# nuc5v2.net
KiCad netlist of a schematic drawn in Altium Designer
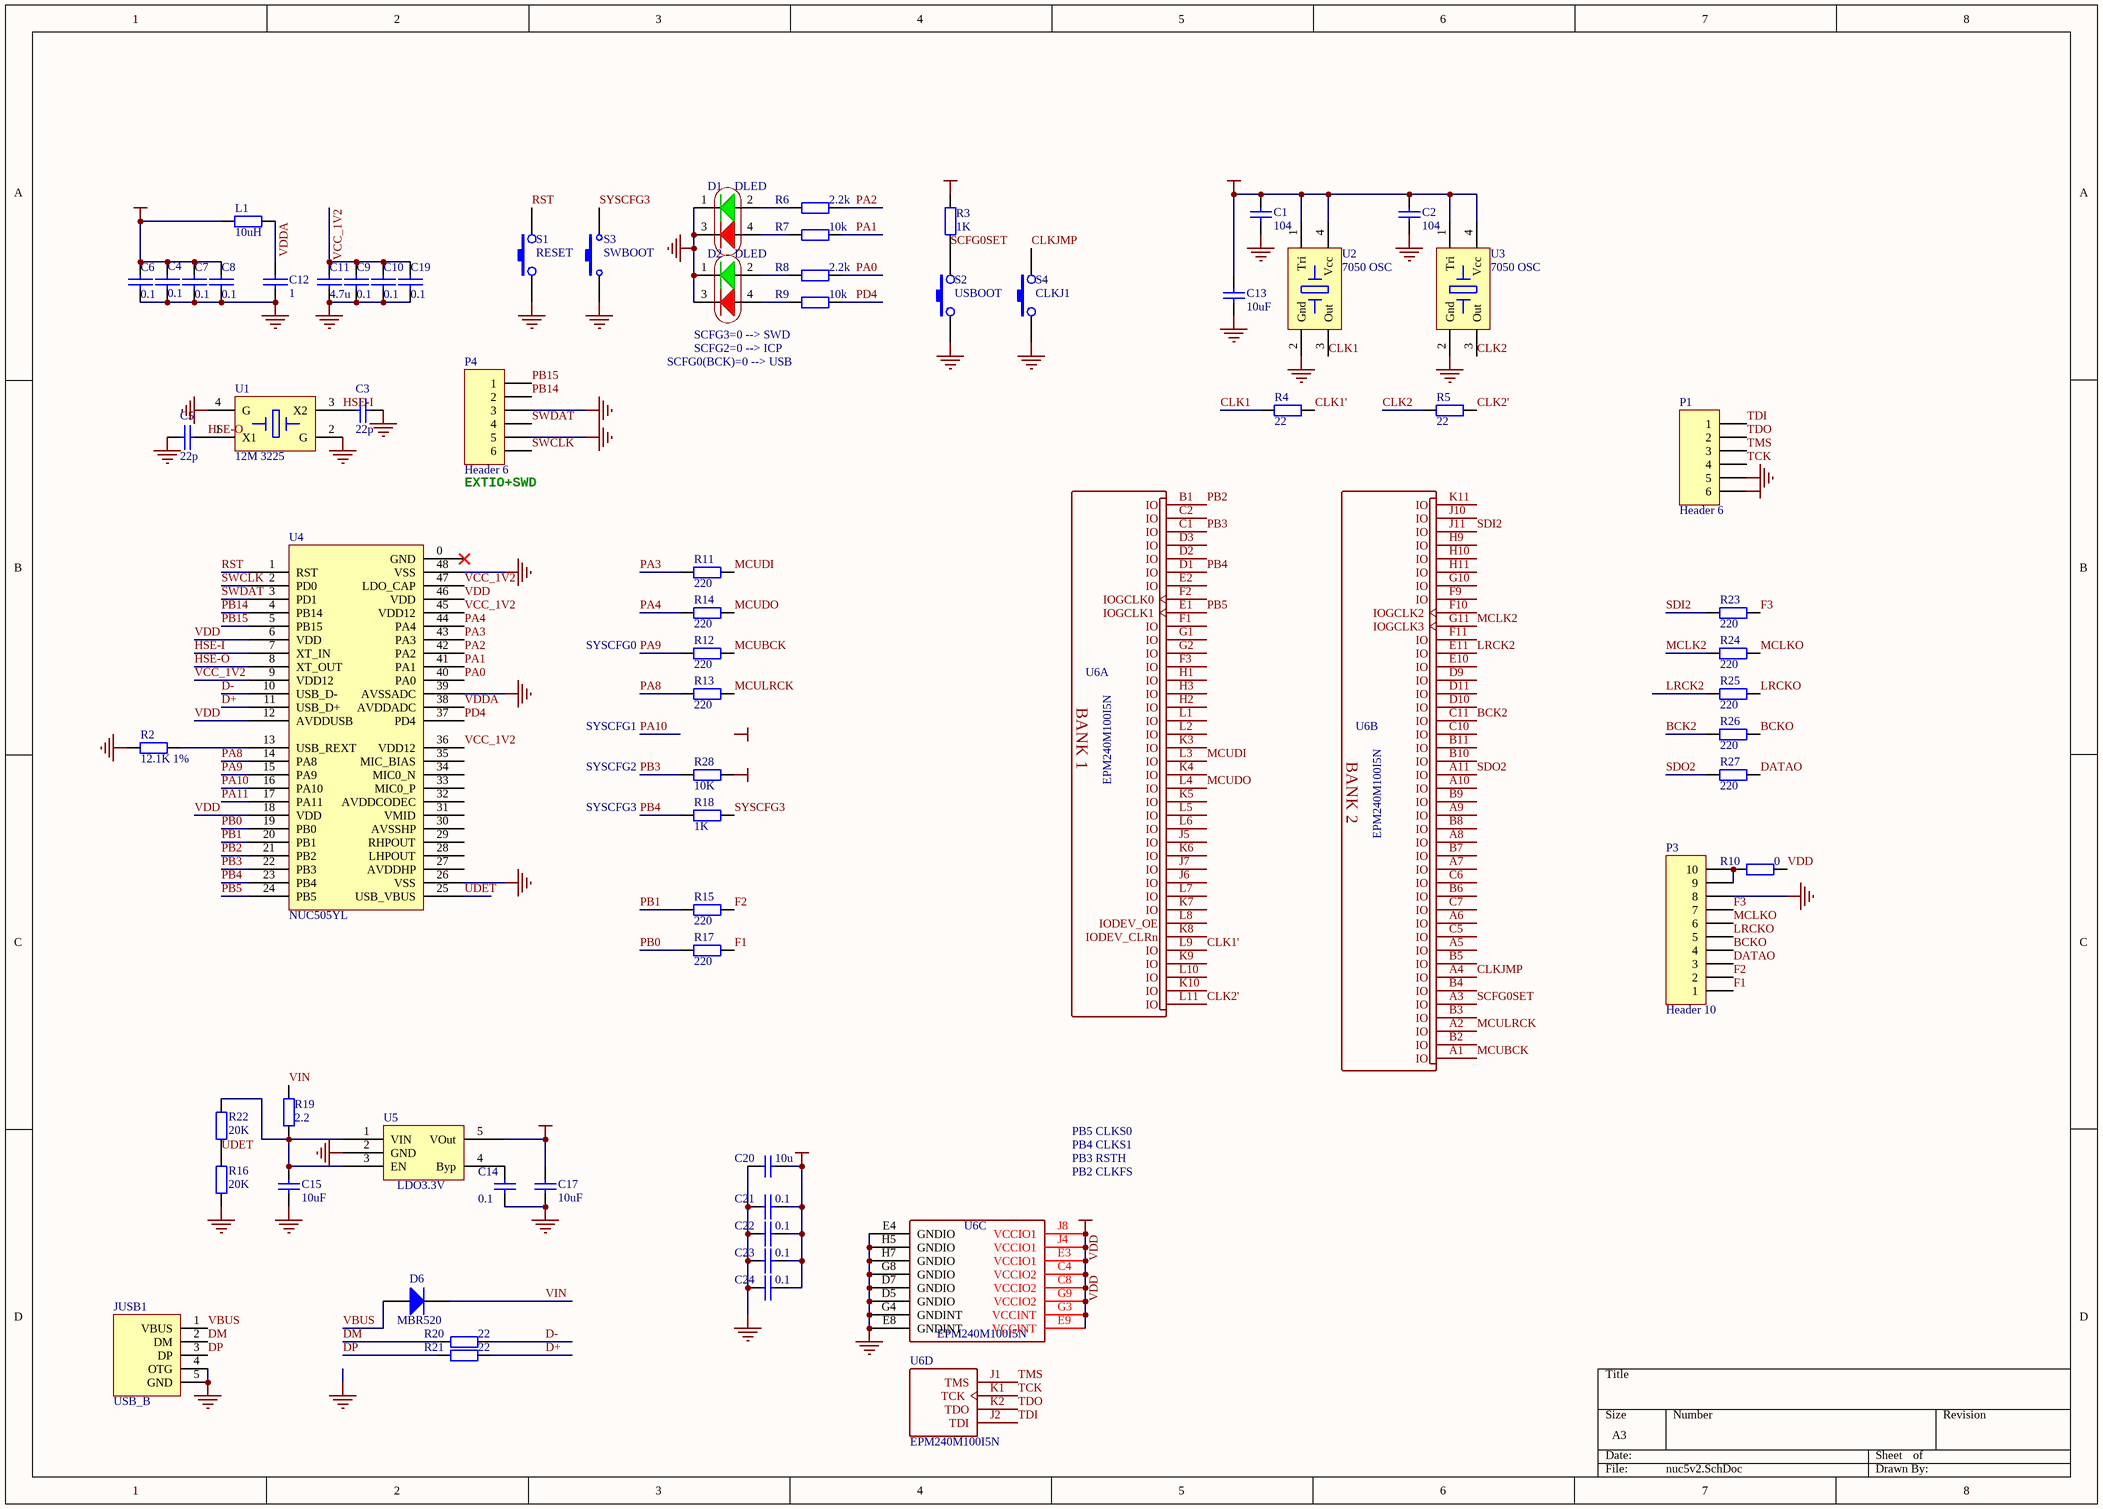
[diagram p0: nuc5v2.SchDoc]

(export (version "E")
  (design (tool "Eeschema 10.0.6"))
  (components
    (comp (ref "C1")
      (value "104")
      (footprint "CC0603CAP")
      (description "Capacitor0603")
      (libsource (lib "ADI1955-Sch") (part "Cap6"))
    )
    (comp (ref "C2")
      (value "104")
      (footprint "CC0603CAP")
      (description "Capacitor0603")
      (libsource (lib "ADI1955-Sch") (part "Cap6"))
    )
    (comp (ref "C3")
      (value "22p")
      (footprint "0603")
      (description "Capacitor")
      (libsource (lib "*") (part "CAP"))
    )
    (comp (ref "C4")
      (value "0.1")
      (footprint "0603")
      (description "Capacitor")
      (libsource (lib "*") (part "CAP"))
    )
    (comp (ref "C5")
      (value "22p")
      (footprint "0603")
      (description "Capacitor")
      (libsource (lib "") (part "CAP_1"))
    )
    (comp (ref "C6")
      (value "0.1")
      (footprint "0603")
      (description "Capacitor")
      (libsource (lib "*") (part "CAP"))
    )
    (comp (ref "C7")
      (value "0.1")
      (footprint "0603")
      (description "Capacitor")
      (libsource (lib "*") (part "CAP"))
    )
    (comp (ref "C8")
      (value "0.1")
      (footprint "0603")
      (description "Capacitor")
      (libsource (lib "*") (part "CAP"))
    )
    (comp (ref "C9")
      (value "0.1")
      (footprint "0603")
      (description "Capacitor")
      (libsource (lib "*") (part "CAP"))
    )
    (comp (ref "C10")
      (value "0.1")
      (footprint "0603")
      (description "Capacitor")
      (libsource (lib "*") (part "CAP"))
    )
    (comp (ref "C11")
      (value "4.7u")
      (footprint "0603")
      (description "Capacitor")
      (libsource (lib "*") (part "CAP"))
    )
    (comp (ref "C12")
      (value "1")
      (footprint "0603")
      (description "Capacitor")
      (libsource (lib "*") (part "CAP"))
    )
    (comp (ref "C13")
      (value "10uF")
      (footprint "CC0805CAP")
      (description "Capacitor0805")
      (libsource (lib "AudioLCR") (part "Cap8"))
    )
    (comp (ref "C14")
      (value "0.1")
      (footprint "0603")
      (description "Capacitor0805")
      (libsource (lib "*") (part "Cap8"))
    )
    (comp (ref "C15")
      (value "10uF")
      (footprint "CC0805CAP")
      (description "Capacitor0805")
      (libsource (lib "AudioLCR") (part "Cap8"))
    )
    (comp (ref "C17")
      (value "10uF")
      (footprint "CC0805CAP")
      (description "Capacitor0805")
      (libsource (lib "AudioLCR") (part "Cap8"))
    )
    (comp (ref "C19")
      (value "0.1")
      (footprint "0603")
      (description "Capacitor")
      (libsource (lib "*") (part "CAP"))
    )
    (comp (ref "C20")
      (value "10u")
      (footprint "CC0805CAP")
      (description "Capacitor0805")
      (libsource (lib "S1-LCR") (part "Cap8"))
    )
    (comp (ref "C21")
      (value "0.1")
      (footprint "0603")
      (description "Capacitor")
      (libsource (lib "*") (part "CAP"))
    )
    (comp (ref "C22")
      (value "0.1")
      (footprint "0603")
      (description "Capacitor")
      (libsource (lib "*") (part "CAP"))
    )
    (comp (ref "C23")
      (value "0.1")
      (footprint "0603")
      (description "Capacitor")
      (libsource (lib "*") (part "CAP"))
    )
    (comp (ref "C24")
      (value "0.1")
      (footprint "0603")
      (description "Capacitor")
      (libsource (lib "*") (part "CAP"))
    )
    (comp (ref "D1")
      (value "DLED")
      (footprint "LED1204")
      (description "1204双色LED")
      (libsource (lib "S1-常用") (part "LED1204"))
    )
    (comp (ref "D2")
      (value "DLED")
      (footprint "LED1204")
      (description "1204双色LED")
      (libsource (lib "S1-常用") (part "LED1204"))
    )
    (comp (ref "D6")
      (value "MBR520")
      (footprint "SOD123")
      (description "Default Diode")
      (libsource (lib "Miscellaneous Devices") (part "Diode"))
    )
    (comp (ref "JUSB1")
      (value "USB_B")
      (footprint "USB-B-M")
      (description "USB Mini/Micro 5P")
      (libsource (lib "AudioLCR") (part "USB_B"))
    )
    (comp (ref "L1")
      (value "10uH")
      (footprint "CC0805RES")
      (description "Resistor0805")
      (libsource (lib "ADI1955-Sch") (part "Res8"))
    )
    (comp (ref "P1")
      (value "Header 6")
      (footprint "密脚针1.27mm*6")
      (description "Header, 6-Pin")
      (fields (field (name "PUBLISHER") "Altium Limited"))
      (libsource (lib "Miscellaneous Connectors") (part "Header 6"))
    )
    (comp (ref "P3")
      (value "Header 10")
      (footprint "HDR1X10")
      (description "Header, 10-Pin")
      (fields (field (name "PUBLISHER") "Altium Limited"))
      (libsource (lib "Miscellaneous Connectors") (part "Header 10"))
    )
    (comp (ref "P4")
      (value "Header 6")
      (footprint "密脚针1.27mm*6")
      (description "Header, 6-Pin")
      (fields (field (name "PUBLISHER") "Altium Limited"))
      (libsource (lib "Miscellaneous Connectors") (part "Header 6"))
    )
    (comp (ref "R2")
      (value "12.1K 1%")
      (footprint "CR1005-0402")
      (description "Resistor0603")
      (libsource (lib "S1-LCR") (part "Res6"))
    )
    (comp (ref "R3")
      (value "1K")
      (footprint "CR1005-0402")
      (description "Resistor0603")
      (libsource (lib "") (part "Res6_1"))
    )
    (comp (ref "R4")
      (value "22")
      (footprint "CR1005-0402")
      (description "Resistor0603")
      (libsource (lib "*") (part "Res6"))
    )
    (comp (ref "R5")
      (value "22")
      (footprint "CR1005-0402")
      (description "Resistor0603")
      (libsource (lib "*") (part "Res6"))
    )
    (comp (ref "R6")
      (value "2.2k")
      (footprint "CR1005-0402")
      (description "Resistor0603")
      (libsource (lib "ADI1955-Sch") (part "Res6"))
    )
    (comp (ref "R7")
      (value "10k")
      (footprint "CR1005-0402")
      (description "Resistor0603")
      (libsource (lib "ADI1955-Sch") (part "Res6"))
    )
    (comp (ref "R8")
      (value "2.2k")
      (footprint "CR1005-0402")
      (description "Resistor0603")
      (libsource (lib "ADI1955-Sch") (part "Res6"))
    )
    (comp (ref "R9")
      (value "10k")
      (footprint "CR1005-0402")
      (description "Resistor0603")
      (libsource (lib "ADI1955-Sch") (part "Res6"))
    )
    (comp (ref "R10")
      (value "0")
      (footprint "0603")
      (description "Resistor0603")
      (libsource (lib "ADI1955-Sch") (part "Res6"))
    )
    (comp (ref "R11")
      (value "220")
      (footprint "CR1005-0402")
      (description "Resistor0603")
      (libsource (lib "*") (part "Res6"))
    )
    (comp (ref "R12")
      (value "220")
      (footprint "CR1005-0402")
      (description "Resistor0603")
      (libsource (lib "") (part "Res6_2"))
    )
    (comp (ref "R13")
      (value "220")
      (footprint "CR1005-0402")
      (description "Resistor0603")
      (libsource (lib "*") (part "Res6"))
    )
    (comp (ref "R14")
      (value "220")
      (footprint "CR1005-0402")
      (description "Resistor0603")
      (libsource (lib "ADI1955-Sch") (part "Res6"))
    )
    (comp (ref "R15")
      (value "220")
      (footprint "CR1005-0402")
      (description "Resistor0603")
      (libsource (lib "ADI1955-Sch") (part "Res6"))
    )
    (comp (ref "R16")
      (value "20K")
      (footprint "CR1005-0402")
      (description "贴片电阻")
      (libsource (lib "MY LIB") (part "R"))
    )
    (comp (ref "R17")
      (value "220")
      (footprint "CR1005-0402")
      (description "Resistor0603")
      (libsource (lib "ADI1955-Sch") (part "Res6"))
    )
    (comp (ref "R18")
      (value "1K")
      (footprint "CR1005-0402")
      (description "Resistor0603")
      (libsource (lib "*") (part "Res6"))
    )
    (comp (ref "R19")
      (value "2.2")
      (footprint "CC0603RES")
      (description "Resistor0603")
      (libsource (lib "AudioLCR") (part "Res6"))
    )
    (comp (ref "R20")
      (value "22")
      (footprint "CR1005-0402")
      (description "Resistor0603")
      (libsource (lib "ADI1955-Sch") (part "Res6"))
    )
    (comp (ref "R21")
      (value "22")
      (footprint "CR1005-0402")
      (description "Resistor0603")
      (libsource (lib "ADI1955-Sch") (part "Res6"))
    )
    (comp (ref "R22")
      (value "20K")
      (footprint "CR1005-0402")
      (description "贴片电阻")
      (libsource (lib "MY LIB") (part "R"))
    )
    (comp (ref "R23")
      (value "220")
      (footprint "CR1005-0402")
      (description "Resistor0603")
      (libsource (lib "*") (part "Res6"))
    )
    (comp (ref "R24")
      (value "220")
      (footprint "CR1005-0402")
      (description "Resistor0603")
      (libsource (lib "ADI1955-Sch") (part "Res6"))
    )
    (comp (ref "R25")
      (value "220")
      (footprint "CR1005-0402")
      (description "Resistor0603")
      (libsource (lib "") (part "Res6_2"))
    )
    (comp (ref "R26")
      (value "220")
      (footprint "CR1005-0402")
      (description "Resistor0603")
      (libsource (lib "*") (part "Res6"))
    )
    (comp (ref "R27")
      (value "220")
      (footprint "CR1005-0402")
      (description "Resistor0603")
      (libsource (lib "*") (part "Res6"))
    )
    (comp (ref "R28")
      (value "10K")
      (footprint "CR1005-0402")
      (description "Resistor0603")
      (libsource (lib "*") (part "Res6"))
    )
    (comp (ref "S1") (value "RESET") (footprint "密脚针1.27mm*2") (libsource (lib "*") (part "SW-PB")))
    (comp (ref "S2") (value "USBOOT") (footprint "密脚针1.27mm*2") (libsource (lib "*") (part "SW-PB")))
    (comp (ref "S3")
      (value "SWBOOT")
      (footprint "密脚针1.27mm*2")
      (description "Switch")
      (fields (field (name "PUBLISHER") "Altium Limited"))
      (libsource (lib "Miscellaneous Devices") (part "SW-PB"))
    )
    (comp (ref "S4") (value "CLKJ1") (footprint "密脚针1.27mm*2") (libsource (lib "*") (part "SW-PB")))
    (comp (ref "U1") (value "12M 3225") (footprint "OSC-3225") (libsource (lib "AudioLCR") (part "XTAL")))
    (comp (ref "U2") (value "7050 OSC") (footprint "OSC-3225") (libsource (lib "AudioLCR") (part "XTAL_OSC")))
    (comp (ref "U3") (value "7050 OSC") (footprint "OSC-3225") (libsource (lib "AudioLCR") (part "XTAL_OSC")))
    (comp (ref "U4") (value "NUC505YL") (footprint "LQFP-48") (libsource (lib "NUC505YL") (part "NUC505YL")))
    (comp (ref "U5")
      (value "LDO3.3V")
      (footprint "SOT23-5")
      (description "LP2985 5V LDO")
      (libsource (lib "ADI1955-Sch") (part "LP2985-5"))
    )
    (comp (ref "U6")
      (value "EPM240M100I5N")
      (footprint "MBGA100")
      (fields (field (name "SUBPART_NO") "1"))
      (libsource (lib "S2-芯片") (part "EPM240M100I5N"))
    )
  )
  (nets
    (net (code "1") (name "/BCK2") (class "Default")
      (node (ref "R26") (pin "1") (pinfunction "1_1") (pintype "passive"))
      (node (ref "U6") (pin "C11") (pinfunction "IO_C11") (pintype "passive"))
    )
    (net (code "2") (name "/BCKO") (class "Default")
      (node (ref "P3") (pin "4") (pinfunction "4_4") (pintype "passive"))
      (node (ref "R26") (pin "2") (pinfunction "2_2") (pintype "passive"))
    )
    (net (code "3") (name "/CLK1") (class "Default")
      (node (ref "R4") (pin "1") (pinfunction "1_1") (pintype "passive"))
      (node (ref "U2") (pin "3") (pinfunction "Out_3") (pintype "passive"))
    )
    (net (code "4") (name "/CLK1'") (class "Default")
      (node (ref "R4") (pin "2") (pinfunction "2_2") (pintype "passive"))
      (node (ref "U6") (pin "L9") (pinfunction "IO_L9") (pintype "passive"))
    )
    (net (code "5") (name "/CLK2") (class "Default")
      (node (ref "R5") (pin "1") (pinfunction "1_1") (pintype "passive"))
      (node (ref "U3") (pin "3") (pinfunction "Out_3") (pintype "passive"))
    )
    (net (code "6") (name "/CLK2'") (class "Default")
      (node (ref "R5") (pin "2") (pinfunction "2_2") (pintype "passive"))
      (node (ref "U6") (pin "L11") (pinfunction "IO_L11") (pintype "passive"))
    )
    (net (code "7") (name "/CLKJMP") (class "Default")
      (node (ref "S4") (pin "2") (pinfunction "2_2") (pintype "passive"))
      (node (ref "U6") (pin "A4") (pinfunction "IO_A4") (pintype "passive"))
    )
    (net (code "8") (name "/D+") (class "Default")
      (node (ref "R21") (pin "1") (pinfunction "1_1") (pintype "passive"))
      (node (ref "U4") (pin "11") (pinfunction "USB_D+_11") (pintype "passive"))
    )
    (net (code "9") (name "/D-") (class "Default")
      (node (ref "R20") (pin "1") (pinfunction "1_1") (pintype "passive"))
      (node (ref "U4") (pin "10") (pinfunction "USB_D-_10") (pintype "passive"))
    )
    (net (code "10") (name "/DATAO") (class "Default")
      (node (ref "P3") (pin "3") (pinfunction "3_3") (pintype "passive"))
      (node (ref "R27") (pin "2") (pinfunction "2_2") (pintype "passive"))
    )
    (net (code "11") (name "/DM") (class "Default")
      (node (ref "JUSB1") (pin "2") (pinfunction "DM_2") (pintype "passive"))
      (node (ref "R20") (pin "2") (pinfunction "2_2") (pintype "passive"))
    )
    (net (code "12") (name "/DP") (class "Default")
      (node (ref "JUSB1") (pin "3") (pinfunction "DP_3") (pintype "passive"))
      (node (ref "R21") (pin "2") (pinfunction "2_2") (pintype "passive"))
    )
    (net (code "13") (name "/F1") (class "Default")
      (node (ref "P3") (pin "1") (pinfunction "1_1") (pintype "passive"))
      (node (ref "R17") (pin "1") (pinfunction "1_1") (pintype "passive"))
    )
    (net (code "14") (name "/F2") (class "Default")
      (node (ref "P3") (pin "2") (pinfunction "2_2") (pintype "passive"))
      (node (ref "R15") (pin "1") (pinfunction "1_1") (pintype "passive"))
    )
    (net (code "15") (name "/F3") (class "Default")
      (node (ref "P3") (pin "7") (pinfunction "7_7") (pintype "passive"))
      (node (ref "R23") (pin "2") (pinfunction "2_2") (pintype "passive"))
    )
    (net (code "16") (name "/HSE-I") (class "Default")
      (node (ref "C3") (pin "1") (pinfunction "1_1") (pintype "passive"))
      (node (ref "U1") (pin "3") (pinfunction "X2_3") (pintype "passive"))
      (node (ref "U4") (pin "7") (pinfunction "XT_IN_7") (pintype "passive"))
    )
    (net (code "17") (name "/HSE-O") (class "Default")
      (node (ref "C5") (pin "2") (pinfunction "2_2") (pintype "passive"))
      (node (ref "U1") (pin "1") (pinfunction "X1_1") (pintype "passive"))
      (node (ref "U4") (pin "8") (pinfunction "XT_OUT_8") (pintype "passive"))
    )
    (net (code "18") (name "/LRCK2") (class "Default")
      (node (ref "R25") (pin "2") (pinfunction "2_2") (pintype "passive"))
      (node (ref "U6") (pin "E11") (pinfunction "IO_E11") (pintype "passive"))
    )
    (net (code "19") (name "/LRCKO") (class "Default")
      (node (ref "P3") (pin "5") (pinfunction "5_5") (pintype "passive"))
      (node (ref "R25") (pin "1") (pinfunction "1_1") (pintype "passive"))
    )
    (net (code "20") (name "/MCLK2") (class "Default")
      (node (ref "R24") (pin "2") (pinfunction "2_2") (pintype "passive"))
      (node (ref "U6") (pin "G11") (pinfunction "IOGCLK3_G11") (pintype "passive"))
    )
    (net (code "21") (name "/MCLKO") (class "Default")
      (node (ref "P3") (pin "6") (pinfunction "6_6") (pintype "passive"))
      (node (ref "R24") (pin "1") (pinfunction "1_1") (pintype "passive"))
    )
    (net (code "22") (name "/MCUBCK") (class "Default")
      (node (ref "R12") (pin "1") (pinfunction "1_1") (pintype "passive"))
      (node (ref "U6") (pin "A1") (pinfunction "IO_A1") (pintype "passive"))
    )
    (net (code "23") (name "/MCUDI") (class "Default")
      (node (ref "R11") (pin "2") (pinfunction "2_2") (pintype "passive"))
      (node (ref "U6") (pin "L3") (pinfunction "IO_L3") (pintype "passive"))
    )
    (net (code "24") (name "/MCUDO") (class "Default")
      (node (ref "R14") (pin "1") (pinfunction "1_1") (pintype "passive"))
      (node (ref "U6") (pin "L4") (pinfunction "IO_L4") (pintype "passive"))
    )
    (net (code "25") (name "/MCULRCK") (class "Default")
      (node (ref "R13") (pin "2") (pinfunction "2_2") (pintype "passive"))
      (node (ref "U6") (pin "A2") (pinfunction "IO_A2") (pintype "passive"))
    )
    (net (code "26") (name "/PA0") (class "Default")
      (node (ref "R8") (pin "1") (pinfunction "1_1") (pintype "passive"))
      (node (ref "U4") (pin "40") (pinfunction "PA0_40") (pintype "passive"))
    )
    (net (code "27") (name "/PA1") (class "Default")
      (node (ref "R7") (pin "1") (pinfunction "1_1") (pintype "passive"))
      (node (ref "U4") (pin "41") (pinfunction "PA1_41") (pintype "passive"))
    )
    (net (code "28") (name "/PA2") (class "Default")
      (node (ref "R6") (pin "1") (pinfunction "1_1") (pintype "passive"))
      (node (ref "U4") (pin "42") (pinfunction "PA2_42") (pintype "passive"))
    )
    (net (code "29") (name "/PA3") (class "Default")
      (node (ref "R11") (pin "1") (pinfunction "1_1") (pintype "passive"))
      (node (ref "U4") (pin "43") (pinfunction "PA3_43") (pintype "passive"))
    )
    (net (code "30") (name "/PA4") (class "Default")
      (node (ref "R14") (pin "2") (pinfunction "2_2") (pintype "passive"))
      (node (ref "U4") (pin "44") (pinfunction "PA4_44") (pintype "passive"))
    )
    (net (code "31") (name "/PA8") (class "Default")
      (node (ref "R13") (pin "1") (pinfunction "1_1") (pintype "passive"))
      (node (ref "U4") (pin "14") (pinfunction "PA8_14") (pintype "passive"))
    )
    (net (code "32") (name "/PA9") (class "Default")
      (node (ref "R12") (pin "2") (pinfunction "2_2") (pintype "passive"))
      (node (ref "U4") (pin "15") (pinfunction "PA9_15") (pintype "passive"))
    )
    (net (code "33") (name "/PA10") (class "Default")
      (node (ref "U4") (pin "16") (pinfunction "PA10_16") (pintype "passive"))
    )
    (net (code "34") (name "/PA11") (class "Default")
      (node (ref "U4") (pin "17") (pinfunction "PA11_17") (pintype "passive"))
    )
    (net (code "35") (name "/PB0") (class "Default")
      (node (ref "R17") (pin "2") (pinfunction "2_2") (pintype "passive"))
      (node (ref "U4") (pin "19") (pinfunction "PB0_19") (pintype "passive"))
    )
    (net (code "36") (name "/PB1") (class "Default")
      (node (ref "R15") (pin "2") (pinfunction "2_2") (pintype "passive"))
      (node (ref "U4") (pin "20") (pinfunction "PB1_20") (pintype "passive"))
    )
    (net (code "37") (name "/PB2") (class "Default")
      (node (ref "U4") (pin "21") (pinfunction "PB2_21") (pintype "passive"))
      (node (ref "U6") (pin "B1") (pinfunction "IO_B1") (pintype "passive"))
    )
    (net (code "38") (name "/PB3") (class "Default")
      (node (ref "R28") (pin "1") (pinfunction "1_1") (pintype "passive"))
      (node (ref "U4") (pin "22") (pinfunction "PB3_22") (pintype "passive"))
      (node (ref "U6") (pin "C1") (pinfunction "IO_C1") (pintype "passive"))
    )
    (net (code "39") (name "/PB4") (class "Default")
      (node (ref "R18") (pin "1") (pinfunction "1_1") (pintype "passive"))
      (node (ref "U4") (pin "23") (pinfunction "PB4_23") (pintype "passive"))
      (node (ref "U6") (pin "D1") (pinfunction "IO_D1") (pintype "passive"))
    )
    (net (code "40") (name "/PB5") (class "Default")
      (node (ref "U4") (pin "24") (pinfunction "PB5_24") (pintype "passive"))
      (node (ref "U6") (pin "E1") (pinfunction "IOGCLK1_E1") (pintype "passive"))
    )
    (net (code "41") (name "/PB14") (class "Default")
      (node (ref "P4") (pin "2") (pinfunction "2_2") (pintype "passive"))
      (node (ref "U4") (pin "4") (pinfunction "PB14_4") (pintype "passive"))
    )
    (net (code "42") (name "/PB15") (class "Default")
      (node (ref "P4") (pin "1") (pinfunction "1_1") (pintype "passive"))
      (node (ref "U4") (pin "5") (pinfunction "PB15_5") (pintype "passive"))
    )
    (net (code "43") (name "/PD4") (class "Default")
      (node (ref "R9") (pin "1") (pinfunction "1_1") (pintype "passive"))
      (node (ref "U4") (pin "37") (pinfunction "PD4_37") (pintype "passive"))
    )
    (net (code "44") (name "/RST") (class "Default")
      (node (ref "S1") (pin "2") (pinfunction "2_2") (pintype "passive"))
      (node (ref "U4") (pin "1") (pinfunction "RST_1") (pintype "passive"))
    )
    (net (code "45") (name "/SCFG0SET") (class "Default")
      (node (ref "R3") (pin "1") (pinfunction "1_1") (pintype "passive"))
      (node (ref "S2") (pin "2") (pinfunction "2_2") (pintype "passive"))
      (node (ref "U6") (pin "A3") (pinfunction "IO_A3") (pintype "passive"))
    )
    (net (code "46") (name "/SDI2") (class "Default")
      (node (ref "R23") (pin "1") (pinfunction "1_1") (pintype "passive"))
      (node (ref "U6") (pin "J11") (pinfunction "IO_J11") (pintype "passive"))
    )
    (net (code "47") (name "/SDO2") (class "Default")
      (node (ref "R27") (pin "1") (pinfunction "1_1") (pintype "passive"))
      (node (ref "U6") (pin "A11") (pinfunction "IO_A11") (pintype "passive"))
    )
    (net (code "48") (name "/SWCLK") (class "Default")
      (node (ref "P4") (pin "6") (pinfunction "6_6") (pintype "passive"))
      (node (ref "U4") (pin "2") (pinfunction "PD0_2") (pintype "passive"))
    )
    (net (code "49") (name "/SWDAT") (class "Default")
      (node (ref "P4") (pin "4") (pinfunction "4_4") (pintype "passive"))
      (node (ref "U4") (pin "3") (pinfunction "PD1_3") (pintype "passive"))
    )
    (net (code "50") (name "/SYSCFG3") (class "Default")
      (node (ref "R18") (pin "2") (pinfunction "2_2") (pintype "passive"))
      (node (ref "S3") (pin "2") (pinfunction "2_2") (pintype "passive"))
    )
    (net (code "51") (name "/TCK") (class "Default")
      (node (ref "P1") (pin "4") (pinfunction "4_4") (pintype "passive"))
      (node (ref "U6") (pin "K1") (pinfunction "TCK_K1") (pintype "passive"))
    )
    (net (code "52") (name "/TDI") (class "Default")
      (node (ref "P1") (pin "1") (pinfunction "1_1") (pintype "passive"))
      (node (ref "U6") (pin "J2") (pinfunction "TDI_J2") (pintype "passive"))
    )
    (net (code "53") (name "/TDO") (class "Default")
      (node (ref "P1") (pin "2") (pinfunction "2_2") (pintype "passive"))
      (node (ref "U6") (pin "K2") (pinfunction "TDO_K2") (pintype "passive"))
    )
    (net (code "54") (name "/TMS") (class "Default")
      (node (ref "P1") (pin "3") (pinfunction "3_3") (pintype "passive"))
      (node (ref "U6") (pin "J1") (pinfunction "TMS_J1") (pintype "passive"))
    )
    (net (code "55") (name "/UDET") (class "Default")
      (node (ref "R16") (pin "2") (pinfunction "2_2") (pintype "passive"))
      (node (ref "R22") (pin "1") (pinfunction "1_1") (pintype "passive"))
      (node (ref "U4") (pin "25") (pinfunction "USB_VBUS_25") (pintype "passive"))
    )
    (net (code "56") (name "/VBUS") (class "Default")
      (node (ref "D6") (pin "1") (pinfunction "A_1") (pintype "passive"))
      (node (ref "JUSB1") (pin "1") (pinfunction "VBUS_1") (pintype "passive"))
    )
    (net (code "57") (name "/VCC_1V2") (class "Default")
      (node (ref "C10") (pin "1") (pinfunction "1_1") (pintype "passive"))
      (node (ref "C11") (pin "1") (pinfunction "1_1") (pintype "passive"))
      (node (ref "C19") (pin "1") (pinfunction "1_1") (pintype "passive"))
      (node (ref "C9") (pin "1") (pinfunction "1_1") (pintype "passive"))
      (node (ref "U4") (pin "36") (pinfunction "VDD12_36") (pintype "passive"))
      (node (ref "U4") (pin "45") (pinfunction "VDD12_45") (pintype "passive"))
      (node (ref "U4") (pin "47") (pinfunction "LDO_CAP_47") (pintype "passive"))
      (node (ref "U4") (pin "9") (pinfunction "VDD12_9") (pintype "passive"))
    )
    (net (code "58") (name "/VDDA") (class "Default")
      (node (ref "C12") (pin "1") (pinfunction "1_1") (pintype "passive"))
      (node (ref "L1") (pin "2") (pinfunction "2_2") (pintype "passive"))
      (node (ref "U4") (pin "38") (pinfunction "AVDDADC_38") (pintype "passive"))
    )
    (net (code "59") (name "/VIN") (class "Default")
      (node (ref "D6") (pin "2") (pinfunction "K_2") (pintype "passive"))
      (node (ref "R19") (pin "1") (pinfunction "1_1") (pintype "passive"))
    )
    (net (code "60") (name "GND") (class "Default")
      (node (ref "C1") (pin "1") (pinfunction "1_1") (pintype "passive"))
      (node (ref "C10") (pin "2") (pinfunction "2_2") (pintype "passive"))
      (node (ref "C11") (pin "2") (pinfunction "2_2") (pintype "passive"))
      (node (ref "C12") (pin "2") (pinfunction "2_2") (pintype "passive"))
      (node (ref "C13") (pin "1") (pinfunction "1_1") (pintype "passive"))
      (node (ref "C14") (pin "2") (pinfunction "2_2") (pintype "passive"))
      (node (ref "C15") (pin "1") (pinfunction "1_1") (pintype "passive"))
      (node (ref "C17") (pin "1") (pinfunction "1_1") (pintype "passive"))
      (node (ref "C19") (pin "2") (pinfunction "2_2") (pintype "passive"))
      (node (ref "C2") (pin "2") (pinfunction "2_2") (pintype "passive"))
      (node (ref "C20") (pin "2") (pinfunction "2_2") (pintype "passive"))
      (node (ref "C21") (pin "1") (pinfunction "1_1") (pintype "passive"))
      (node (ref "C22") (pin "1") (pinfunction "1_1") (pintype "passive"))
      (node (ref "C23") (pin "1") (pinfunction "1_1") (pintype "passive"))
      (node (ref "C24") (pin "1") (pinfunction "1_1") (pintype "passive"))
      (node (ref "C3") (pin "2") (pinfunction "2_2") (pintype "passive"))
      (node (ref "C4") (pin "2") (pinfunction "2_2") (pintype "passive"))
      (node (ref "C5") (pin "1") (pinfunction "1_1") (pintype "passive"))
      (node (ref "C6") (pin "2") (pinfunction "2_2") (pintype "passive"))
      (node (ref "C7") (pin "1") (pinfunction "1_1") (pintype "passive"))
      (node (ref "C8") (pin "2") (pinfunction "2_2") (pintype "passive"))
      (node (ref "C9") (pin "2") (pinfunction "2_2") (pintype "passive"))
      (node (ref "D1") (pin "1") (pinfunction "1_1") (pintype "passive"))
      (node (ref "D1") (pin "3") (pinfunction "3_3") (pintype "passive"))
      (node (ref "D2") (pin "1") (pinfunction "1_1") (pintype "passive"))
      (node (ref "D2") (pin "3") (pinfunction "3_3") (pintype "passive"))
      (node (ref "JUSB1") (pin "4") (pinfunction "OTG_4") (pintype "passive"))
      (node (ref "JUSB1") (pin "5") (pinfunction "GND_5") (pintype "passive"))
      (node (ref "P1") (pin "5") (pinfunction "5_5") (pintype "passive"))
      (node (ref "P3") (pin "8") (pinfunction "8_8") (pintype "passive"))
      (node (ref "P4") (pin "3") (pinfunction "3_3") (pintype "passive"))
      (node (ref "P4") (pin "5") (pinfunction "5_5") (pintype "passive"))
      (node (ref "R16") (pin "1") (pinfunction "1_1") (pintype "passive"))
      (node (ref "R2") (pin "2") (pinfunction "2_2") (pintype "passive"))
      (node (ref "S1") (pin "1") (pinfunction "1_1") (pintype "passive"))
      (node (ref "S2") (pin "1") (pinfunction "1_1") (pintype "passive"))
      (node (ref "S3") (pin "1") (pinfunction "1_1") (pintype "passive"))
      (node (ref "S4") (pin "1") (pinfunction "1_1") (pintype "passive"))
      (node (ref "U1") (pin "2") (pinfunction "G_2") (pintype "passive"))
      (node (ref "U1") (pin "4") (pinfunction "G_4") (pintype "passive"))
      (node (ref "U2") (pin "2") (pinfunction "Gnd_2") (pintype "passive"))
      (node (ref "U3") (pin "2") (pinfunction "Gnd_2") (pintype "passive"))
      (node (ref "U4") (pin "26") (pinfunction "VSS_26") (pintype "passive"))
      (node (ref "U4") (pin "39") (pinfunction "AVSSADC_39") (pintype "passive"))
      (node (ref "U4") (pin "48") (pinfunction "VSS_48") (pintype "passive"))
      (node (ref "U5") (pin "2") (pinfunction "GND_2") (pintype "passive"))
      (node (ref "U6") (pin "D5") (pinfunction "GNDIO_D5") (pintype "passive"))
      (node (ref "U6") (pin "D7") (pinfunction "GNDIO_D7") (pintype "passive"))
      (node (ref "U6") (pin "E4") (pinfunction "GNDIO_E4") (pintype "passive"))
      (node (ref "U6") (pin "E8") (pinfunction "GNDINT_E8") (pintype "passive"))
      (node (ref "U6") (pin "G4") (pinfunction "GNDINT_G4") (pintype "passive"))
      (node (ref "U6") (pin "G8") (pinfunction "GNDIO_G8") (pintype "passive"))
      (node (ref "U6") (pin "H5") (pinfunction "GNDIO_H5") (pintype "passive"))
      (node (ref "U6") (pin "H7") (pinfunction "GNDIO_H7") (pintype "passive"))
    )
    (net (code "61") (name "Net-(D1-Pad2)") (class "Default")
      (node (ref "D1") (pin "2") (pinfunction "2_2") (pintype "passive"))
      (node (ref "R6") (pin "2") (pinfunction "2_2") (pintype "passive"))
    )
    (net (code "62") (name "Net-(D1-Pad4)") (class "Default")
      (node (ref "D1") (pin "4") (pinfunction "4_4") (pintype "passive"))
      (node (ref "R7") (pin "2") (pinfunction "2_2") (pintype "passive"))
    )
    (net (code "63") (name "Net-(D2-Pad2)") (class "Default")
      (node (ref "D2") (pin "2") (pinfunction "2_2") (pintype "passive"))
      (node (ref "R8") (pin "2") (pinfunction "2_2") (pintype "passive"))
    )
    (net (code "64") (name "Net-(D2-Pad4)") (class "Default")
      (node (ref "D2") (pin "4") (pinfunction "4_4") (pintype "passive"))
      (node (ref "R9") (pin "2") (pinfunction "2_2") (pintype "passive"))
    )
    (net (code "65") (name "Net-(P3-Pad10)") (class "Default")
      (node (ref "P3") (pin "10") (pinfunction "10_10") (pintype "passive"))
      (node (ref "P3") (pin "9") (pinfunction "9_9") (pintype "passive"))
      (node (ref "R10") (pin "2") (pinfunction "2_2") (pintype "passive"))
    )
    (net (code "66") (name "Net-(U4-USB_REXT)") (class "Default")
      (node (ref "R2") (pin "1") (pinfunction "1_1") (pintype "passive"))
      (node (ref "U4") (pin "13") (pinfunction "USB_REXT_13") (pintype "passive"))
    )
    (net (code "67") (name "Net-(U5-Byp)") (class "Default")
      (node (ref "C14") (pin "1") (pinfunction "1_1") (pintype "passive"))
      (node (ref "U5") (pin "4") (pinfunction "Byp_4") (pintype "passive"))
    )
    (net (code "68") (name "Net-(U5-EN)") (class "Default")
      (node (ref "C15") (pin "2") (pinfunction "2_2") (pintype "passive"))
      (node (ref "R19") (pin "2") (pinfunction "2_2") (pintype "passive"))
      (node (ref "R22") (pin "2") (pinfunction "2_2") (pintype "passive"))
      (node (ref "U5") (pin "1") (pinfunction "VIN_1") (pintype "passive"))
      (node (ref "U5") (pin "3") (pinfunction "EN_3") (pintype "passive"))
    )
    (net (code "69") (name "VDD") (class "Default")
      (node (ref "C1") (pin "2") (pinfunction "2_2") (pintype "passive"))
      (node (ref "C13") (pin "2") (pinfunction "2_2") (pintype "passive"))
      (node (ref "C17") (pin "2") (pinfunction "2_2") (pintype "passive"))
      (node (ref "C2") (pin "1") (pinfunction "1_1") (pintype "passive"))
      (node (ref "C20") (pin "1") (pinfunction "1_1") (pintype "passive"))
      (node (ref "C21") (pin "2") (pinfunction "2_2") (pintype "passive"))
      (node (ref "C22") (pin "2") (pinfunction "2_2") (pintype "passive"))
      (node (ref "C23") (pin "2") (pinfunction "2_2") (pintype "passive"))
      (node (ref "C24") (pin "2") (pinfunction "2_2") (pintype "passive"))
      (node (ref "C4") (pin "1") (pinfunction "1_1") (pintype "passive"))
      (node (ref "C6") (pin "1") (pinfunction "1_1") (pintype "passive"))
      (node (ref "C7") (pin "2") (pinfunction "2_2") (pintype "passive"))
      (node (ref "C8") (pin "1") (pinfunction "1_1") (pintype "passive"))
      (node (ref "L1") (pin "1") (pinfunction "1_1") (pintype "passive"))
      (node (ref "P1") (pin "6") (pinfunction "6_6") (pintype "passive"))
      (node (ref "R10") (pin "1") (pinfunction "1_1") (pintype "passive"))
      (node (ref "R28") (pin "2") (pinfunction "2_2") (pintype "passive"))
      (node (ref "R3") (pin "2") (pinfunction "2_2") (pintype "passive"))
      (node (ref "U2") (pin "1") (pinfunction "Tri_1") (pintype "passive"))
      (node (ref "U2") (pin "4") (pinfunction "Vcc_4") (pintype "passive"))
      (node (ref "U3") (pin "1") (pinfunction "Tri_1") (pintype "passive"))
      (node (ref "U3") (pin "4") (pinfunction "Vcc_4") (pintype "passive"))
      (node (ref "U4") (pin "12") (pinfunction "AVDDUSB_12") (pintype "passive"))
      (node (ref "U4") (pin "18") (pinfunction "VDD_18") (pintype "passive"))
      (node (ref "U4") (pin "46") (pinfunction "VDD_46") (pintype "passive"))
      (node (ref "U4") (pin "6") (pinfunction "VDD_6") (pintype "passive"))
      (node (ref "U5") (pin "5") (pinfunction "VOut_5") (pintype "passive"))
      (node (ref "U6") (pin "C4") (pinfunction "VCCIO2_C4") (pintype "passive"))
      (node (ref "U6") (pin "C8") (pinfunction "VCCIO2_C8") (pintype "passive"))
      (node (ref "U6") (pin "E3") (pinfunction "VCCIO1_E3") (pintype "passive"))
      (node (ref "U6") (pin "E9") (pinfunction "VCCINT_E9") (pintype "passive"))
      (node (ref "U6") (pin "G3") (pinfunction "VCCINT_G3") (pintype "passive"))
      (node (ref "U6") (pin "G9") (pinfunction "VCCIO2_G9") (pintype "passive"))
      (node (ref "U6") (pin "J4") (pinfunction "VCCIO1_J4") (pintype "passive"))
      (node (ref "U6") (pin "J8") (pinfunction "VCCIO1_J8") (pintype "passive"))
    )
    (net (code "70") (name "unconnected-(U4-AVDDCODEC-Pad32)") (class "Default")
      (node (ref "U4") (pin "32") (pinfunction "AVDDCODEC_32") (pintype "passive"))
    )
    (net (code "71") (name "unconnected-(U4-AVDDHP-Pad27)") (class "Default")
      (node (ref "U4") (pin "27") (pinfunction "AVDDHP_27") (pintype "passive"))
    )
    (net (code "72") (name "unconnected-(U4-AVSSHP-Pad30)") (class "Default")
      (node (ref "U4") (pin "30") (pinfunction "AVSSHP_30") (pintype "passive"))
    )
    (net (code "73") (name "unconnected-(U4-GND-Pad0)") (class "Default")
      (node (ref "U4") (pin "0") (pinfunction "GND_0") (pintype "passive+no_connect"))
    )
    (net (code "74") (name "unconnected-(U4-LHPOUT-Pad28)") (class "Default")
      (node (ref "U4") (pin "28") (pinfunction "LHPOUT_28") (pintype "passive"))
    )
    (net (code "75") (name "unconnected-(U4-MIC0_N-Pad34)") (class "Default")
      (node (ref "U4") (pin "34") (pinfunction "MIC0_N_34") (pintype "passive"))
    )
    (net (code "76") (name "unconnected-(U4-MIC0_P-Pad33)") (class "Default")
      (node (ref "U4") (pin "33") (pinfunction "MIC0_P_33") (pintype "passive"))
    )
    (net (code "77") (name "unconnected-(U4-MIC_BIAS-Pad35)") (class "Default")
      (node (ref "U4") (pin "35") (pinfunction "MIC_BIAS_35") (pintype "passive"))
    )
    (net (code "78") (name "unconnected-(U4-RHPOUT-Pad29)") (class "Default")
      (node (ref "U4") (pin "29") (pinfunction "RHPOUT_29") (pintype "passive"))
    )
    (net (code "79") (name "unconnected-(U4-VMID-Pad31)") (class "Default")
      (node (ref "U4") (pin "31") (pinfunction "VMID_31") (pintype "passive"))
    )
    (net (code "80") (name "unconnected-(U6A-IO-PadC2)") (class "Default")
      (node (ref "U6") (pin "C2") (pinfunction "IO_C2") (pintype "passive"))
    )
    (net (code "81") (name "unconnected-(U6A-IO-PadD2)") (class "Default")
      (node (ref "U6") (pin "D2") (pinfunction "IO_D2") (pintype "passive"))
    )
    (net (code "82") (name "unconnected-(U6A-IO-PadD3)") (class "Default")
      (node (ref "U6") (pin "D3") (pinfunction "IO_D3") (pintype "passive"))
    )
    (net (code "83") (name "unconnected-(U6A-IO-PadE2)") (class "Default")
      (node (ref "U6") (pin "E2") (pinfunction "IO_E2") (pintype "passive"))
    )
    (net (code "84") (name "unconnected-(U6A-IO-PadF1)") (class "Default")
      (node (ref "U6") (pin "F1") (pinfunction "IO_F1") (pintype "passive"))
    )
    (net (code "85") (name "unconnected-(U6A-IO-PadF3)") (class "Default")
      (node (ref "U6") (pin "F3") (pinfunction "IO_F3") (pintype "passive"))
    )
    (net (code "86") (name "unconnected-(U6A-IO-PadG1)") (class "Default")
      (node (ref "U6") (pin "G1") (pinfunction "IO_G1") (pintype "passive"))
    )
    (net (code "87") (name "unconnected-(U6A-IO-PadG2)") (class "Default")
      (node (ref "U6") (pin "G2") (pinfunction "IO_G2") (pintype "passive"))
    )
    (net (code "88") (name "unconnected-(U6A-IO-PadH1)") (class "Default")
      (node (ref "U6") (pin "H1") (pinfunction "IO_H1") (pintype "passive"))
    )
    (net (code "89") (name "unconnected-(U6A-IO-PadH2)") (class "Default")
      (node (ref "U6") (pin "H2") (pinfunction "IO_H2") (pintype "passive"))
    )
    (net (code "90") (name "unconnected-(U6A-IO-PadH3)") (class "Default")
      (node (ref "U6") (pin "H3") (pinfunction "IO_H3") (pintype "passive"))
    )
    (net (code "91") (name "unconnected-(U6A-IO-PadJ5)") (class "Default")
      (node (ref "U6") (pin "J5") (pinfunction "IO_J5") (pintype "passive"))
    )
    (net (code "92") (name "unconnected-(U6A-IO-PadJ6)") (class "Default")
      (node (ref "U6") (pin "J6") (pinfunction "IO_J6") (pintype "passive"))
    )
    (net (code "93") (name "unconnected-(U6A-IO-PadJ7)") (class "Default")
      (node (ref "U6") (pin "J7") (pinfunction "IO_J7") (pintype "passive"))
    )
    (net (code "94") (name "unconnected-(U6A-IO-PadK3)") (class "Default")
      (node (ref "U6") (pin "K3") (pinfunction "IO_K3") (pintype "passive"))
    )
    (net (code "95") (name "unconnected-(U6A-IO-PadK4)") (class "Default")
      (node (ref "U6") (pin "K4") (pinfunction "IO_K4") (pintype "passive"))
    )
    (net (code "96") (name "unconnected-(U6A-IO-PadK5)") (class "Default")
      (node (ref "U6") (pin "K5") (pinfunction "IO_K5") (pintype "passive"))
    )
    (net (code "97") (name "unconnected-(U6A-IO-PadK6)") (class "Default")
      (node (ref "U6") (pin "K6") (pinfunction "IO_K6") (pintype "passive"))
    )
    (net (code "98") (name "unconnected-(U6A-IO-PadK7)") (class "Default")
      (node (ref "U6") (pin "K7") (pinfunction "IO_K7") (pintype "passive"))
    )
    (net (code "99") (name "unconnected-(U6A-IO-PadK9)") (class "Default")
      (node (ref "U6") (pin "K9") (pinfunction "IO_K9") (pintype "passive"))
    )
    (net (code "100") (name "unconnected-(U6A-IO-PadK10)") (class "Default")
      (node (ref "U6") (pin "K10") (pinfunction "IO_K10") (pintype "passive"))
    )
    (net (code "101") (name "unconnected-(U6A-IO-PadL1)") (class "Default")
      (node (ref "U6") (pin "L1") (pinfunction "IO_L1") (pintype "passive"))
    )
    (net (code "102") (name "unconnected-(U6A-IO-PadL2)") (class "Default")
      (node (ref "U6") (pin "L2") (pinfunction "IO_L2") (pintype "passive"))
    )
    (net (code "103") (name "unconnected-(U6A-IO-PadL5)") (class "Default")
      (node (ref "U6") (pin "L5") (pinfunction "IO_L5") (pintype "passive"))
    )
    (net (code "104") (name "unconnected-(U6A-IO-PadL6)") (class "Default")
      (node (ref "U6") (pin "L6") (pinfunction "IO_L6") (pintype "passive"))
    )
    (net (code "105") (name "unconnected-(U6A-IO-PadL7)") (class "Default")
      (node (ref "U6") (pin "L7") (pinfunction "IO_L7") (pintype "passive"))
    )
    (net (code "106") (name "unconnected-(U6A-IO-PadL10)") (class "Default")
      (node (ref "U6") (pin "L10") (pinfunction "IO_L10") (pintype "passive"))
    )
    (net (code "107") (name "unconnected-(U6A-IODEV_CLRn-PadK8)") (class "Default")
      (node (ref "U6") (pin "K8") (pinfunction "IODEV_CLRn_K8") (pintype "passive"))
    )
    (net (code "108") (name "unconnected-(U6A-IODEV_OE-PadL8)") (class "Default")
      (node (ref "U6") (pin "L8") (pinfunction "IODEV_OE_L8") (pintype "passive"))
    )
    (net (code "109") (name "unconnected-(U6A-IOGCLK0-PadF2)") (class "Default")
      (node (ref "U6") (pin "F2") (pinfunction "IOGCLK0_F2") (pintype "passive"))
    )
    (net (code "110") (name "unconnected-(U6B-IO-PadA5)") (class "Default")
      (node (ref "U6") (pin "A5") (pinfunction "IO_A5") (pintype "passive"))
    )
    (net (code "111") (name "unconnected-(U6B-IO-PadA6)") (class "Default")
      (node (ref "U6") (pin "A6") (pinfunction "IO_A6") (pintype "passive"))
    )
    (net (code "112") (name "unconnected-(U6B-IO-PadA7)") (class "Default")
      (node (ref "U6") (pin "A7") (pinfunction "IO_A7") (pintype "passive"))
    )
    (net (code "113") (name "unconnected-(U6B-IO-PadA8)") (class "Default")
      (node (ref "U6") (pin "A8") (pinfunction "IO_A8") (pintype "passive"))
    )
    (net (code "114") (name "unconnected-(U6B-IO-PadA9)") (class "Default")
      (node (ref "U6") (pin "A9") (pinfunction "IO_A9") (pintype "passive"))
    )
    (net (code "115") (name "unconnected-(U6B-IO-PadA10)") (class "Default")
      (node (ref "U6") (pin "A10") (pinfunction "IO_A10") (pintype "passive"))
    )
    (net (code "116") (name "unconnected-(U6B-IO-PadB2)") (class "Default")
      (node (ref "U6") (pin "B2") (pinfunction "IO_B2") (pintype "passive"))
    )
    (net (code "117") (name "unconnected-(U6B-IO-PadB3)") (class "Default")
      (node (ref "U6") (pin "B3") (pinfunction "IO_B3") (pintype "passive"))
    )
    (net (code "118") (name "unconnected-(U6B-IO-PadB4)") (class "Default")
      (node (ref "U6") (pin "B4") (pinfunction "IO_B4") (pintype "passive"))
    )
    (net (code "119") (name "unconnected-(U6B-IO-PadB5)") (class "Default")
      (node (ref "U6") (pin "B5") (pinfunction "IO_B5") (pintype "passive"))
    )
    (net (code "120") (name "unconnected-(U6B-IO-PadB6)") (class "Default")
      (node (ref "U6") (pin "B6") (pinfunction "IO_B6") (pintype "passive"))
    )
    (net (code "121") (name "unconnected-(U6B-IO-PadB7)") (class "Default")
      (node (ref "U6") (pin "B7") (pinfunction "IO_B7") (pintype "passive"))
    )
    (net (code "122") (name "unconnected-(U6B-IO-PadB8)") (class "Default")
      (node (ref "U6") (pin "B8") (pinfunction "IO_B8") (pintype "passive"))
    )
    (net (code "123") (name "unconnected-(U6B-IO-PadB9)") (class "Default")
      (node (ref "U6") (pin "B9") (pinfunction "IO_B9") (pintype "passive"))
    )
    (net (code "124") (name "unconnected-(U6B-IO-PadB10)") (class "Default")
      (node (ref "U6") (pin "B10") (pinfunction "IO_B10") (pintype "passive"))
    )
    (net (code "125") (name "unconnected-(U6B-IO-PadB11)") (class "Default")
      (node (ref "U6") (pin "B11") (pinfunction "IO_B11") (pintype "passive"))
    )
    (net (code "126") (name "unconnected-(U6B-IO-PadC5)") (class "Default")
      (node (ref "U6") (pin "C5") (pinfunction "IO_C5") (pintype "passive"))
    )
    (net (code "127") (name "unconnected-(U6B-IO-PadC6)") (class "Default")
      (node (ref "U6") (pin "C6") (pinfunction "IO_C6") (pintype "passive"))
    )
    (net (code "128") (name "unconnected-(U6B-IO-PadC7)") (class "Default")
      (node (ref "U6") (pin "C7") (pinfunction "IO_C7") (pintype "passive"))
    )
    (net (code "129") (name "unconnected-(U6B-IO-PadC10)") (class "Default")
      (node (ref "U6") (pin "C10") (pinfunction "IO_C10") (pintype "passive"))
    )
    (net (code "130") (name "unconnected-(U6B-IO-PadD9)") (class "Default")
      (node (ref "U6") (pin "D9") (pinfunction "IO_D9") (pintype "passive"))
    )
    (net (code "131") (name "unconnected-(U6B-IO-PadD10)") (class "Default")
      (node (ref "U6") (pin "D10") (pinfunction "IO_D10") (pintype "passive"))
    )
    (net (code "132") (name "unconnected-(U6B-IO-PadD11)") (class "Default")
      (node (ref "U6") (pin "D11") (pinfunction "IO_D11") (pintype "passive"))
    )
    (net (code "133") (name "unconnected-(U6B-IO-PadE10)") (class "Default")
      (node (ref "U6") (pin "E10") (pinfunction "IO_E10") (pintype "passive"))
    )
    (net (code "134") (name "unconnected-(U6B-IO-PadF9)") (class "Default")
      (node (ref "U6") (pin "F9") (pinfunction "IO_F9") (pintype "passive"))
    )
    (net (code "135") (name "unconnected-(U6B-IO-PadF11)") (class "Default")
      (node (ref "U6") (pin "F11") (pinfunction "IO_F11") (pintype "passive"))
    )
    (net (code "136") (name "unconnected-(U6B-IO-PadG10)") (class "Default")
      (node (ref "U6") (pin "G10") (pinfunction "IO_G10") (pintype "passive"))
    )
    (net (code "137") (name "unconnected-(U6B-IO-PadH9)") (class "Default")
      (node (ref "U6") (pin "H9") (pinfunction "IO_H9") (pintype "passive"))
    )
    (net (code "138") (name "unconnected-(U6B-IO-PadH10)") (class "Default")
      (node (ref "U6") (pin "H10") (pinfunction "IO_H10") (pintype "passive"))
    )
    (net (code "139") (name "unconnected-(U6B-IO-PadH11)") (class "Default")
      (node (ref "U6") (pin "H11") (pinfunction "IO_H11") (pintype "passive"))
    )
    (net (code "140") (name "unconnected-(U6B-IO-PadJ10)") (class "Default")
      (node (ref "U6") (pin "J10") (pinfunction "IO_J10") (pintype "passive"))
    )
    (net (code "141") (name "unconnected-(U6B-IO-PadK11)") (class "Default")
      (node (ref "U6") (pin "K11") (pinfunction "IO_K11") (pintype "passive"))
    )
    (net (code "142") (name "unconnected-(U6B-IOGCLK2-PadF10)") (class "Default")
      (node (ref "U6") (pin "F10") (pinfunction "IOGCLK2_F10") (pintype "passive"))
    )
  )
)
